# ZYNQ_PWR.net
KiCad netlist of a schematic drawn in Altium Designer
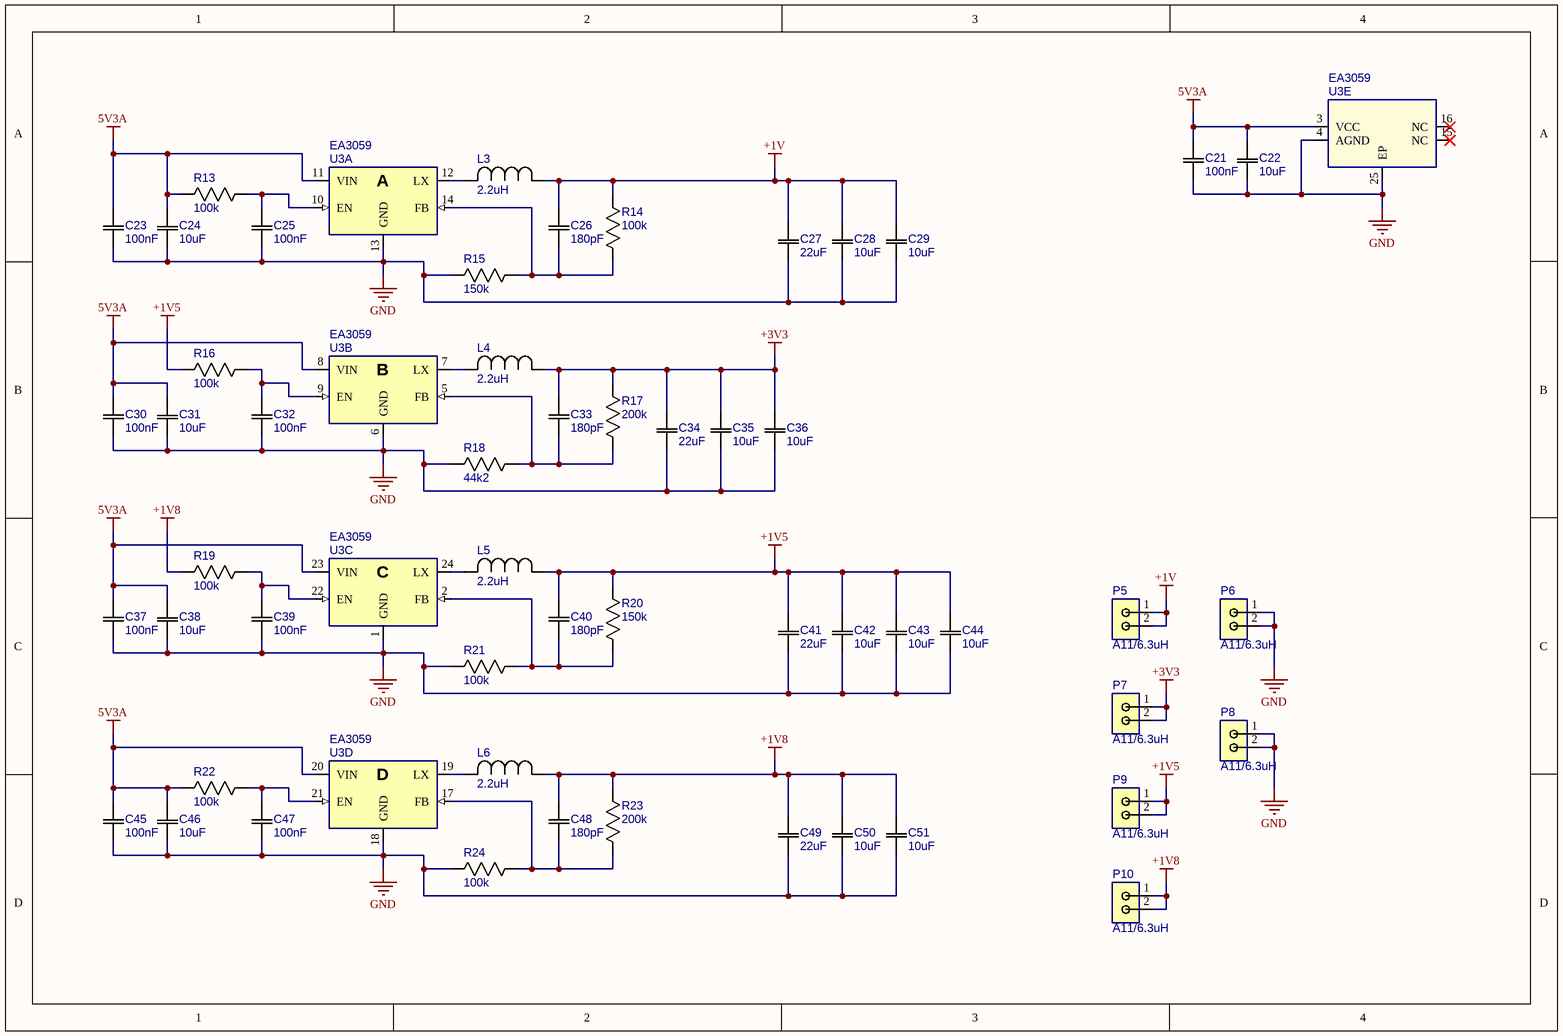
[diagram p0: ZYNQ_PWR.SchDoc]

(export (version "E")
  (design (tool "Eeschema 10.0.6"))
  (components
    (comp (ref "C21")
      (value "100nF")
      (footprint "0402")
      (description "GCM155R71H104ME02J\r\nMultilayer Ceramic Capacitors MLCC - SMD/SMT")
      (fields (field (name "MFR.") "Murata Electronics"))
      (libsource (lib "C0402") (part "GCM155R71H104ME02J"))
    )
    (comp (ref "C22")
      (value "10uF")
      (footprint "C0603")
      (description "OUDEIBUN\r\n50V 10% 106K X5R")
      (fields (field (name "MFR.") "OUDEIBUN"))
      (libsource (lib "C0603") (part "taobao_10uF"))
    )
    (comp (ref "C23")
      (value "100nF")
      (footprint "0402")
      (description "GCM155R71H104ME02J\r\nMultilayer Ceramic Capacitors MLCC - SMD/SMT")
      (fields (field (name "MFR.") "Murata Electronics"))
      (libsource (lib "C0402") (part "GCM155R71H104ME02J"))
    )
    (comp (ref "C24")
      (value "10uF")
      (footprint "C0603")
      (description "OUDEIBUN\r\n50V 10% 106K X5R")
      (fields (field (name "MFR.") "OUDEIBUN"))
      (libsource (lib "C0603") (part "taobao_10uF"))
    )
    (comp (ref "C25")
      (value "100nF")
      (footprint "0402")
      (description "GCM155R71H104ME02J\r\nMultilayer Ceramic Capacitors MLCC - SMD/SMT")
      (fields (field (name "MFR.") "Murata Electronics"))
      (libsource (lib "C0402") (part "GCM155R71H104ME02J"))
    )
    (comp (ref "C26")
      (value "180pF")
      (footprint "0402")
      (description "CL05C181JB5NNNC\r\n180pF(181) +/-5% 50V C0G")
      (fields (field (name "MFR.") "CL05C181JB5NNNC"))
      (libsource (lib "C0402") (part "CL05C181JB5NNNC"))
    )
    (comp (ref "C27")
      (value "22uF")
      (footprint "C0603")
      (description "OUDEIBUN\r\n25V 10% 226K X5R")
      (fields (field (name "MFR.") "OUDEIBUN"))
      (libsource (lib "C0603") (part "taobao_22uF"))
    )
    (comp (ref "C28")
      (value "10uF")
      (footprint "C0603")
      (description "OUDEIBUN\r\n50V 10% 106K X5R")
      (fields (field (name "MFR.") "OUDEIBUN"))
      (libsource (lib "C0603") (part "taobao_10uF"))
    )
    (comp (ref "C29")
      (value "10uF")
      (footprint "C0603")
      (description "OUDEIBUN\r\n50V 10% 106K X5R")
      (fields (field (name "MFR.") "OUDEIBUN"))
      (libsource (lib "C0603") (part "taobao_10uF"))
    )
    (comp (ref "C30")
      (value "100nF")
      (footprint "0402")
      (description "GCM155R71H104ME02J\r\nMultilayer Ceramic Capacitors MLCC - SMD/SMT")
      (fields (field (name "MFR.") "Murata Electronics"))
      (libsource (lib "C0402") (part "GCM155R71H104ME02J"))
    )
    (comp (ref "C31")
      (value "10uF")
      (footprint "C0603")
      (description "OUDEIBUN\r\n50V 10% 106K X5R")
      (fields (field (name "MFR.") "OUDEIBUN"))
      (libsource (lib "C0603") (part "taobao_10uF"))
    )
    (comp (ref "C32")
      (value "100nF")
      (footprint "0402")
      (description "GCM155R71H104ME02J\r\nMultilayer Ceramic Capacitors MLCC - SMD/SMT")
      (fields (field (name "MFR.") "Murata Electronics"))
      (libsource (lib "C0402") (part "GCM155R71H104ME02J"))
    )
    (comp (ref "C33")
      (value "180pF")
      (footprint "0402")
      (description "CL05C181JB5NNNC\r\n180pF(181) +/-5% 50V C0G")
      (fields (field (name "MFR.") "CL05C181JB5NNNC"))
      (libsource (lib "C0402") (part "CL05C181JB5NNNC"))
    )
    (comp (ref "C34")
      (value "22uF")
      (footprint "C0603")
      (description "OUDEIBUN\r\n25V 10% 226K X5R")
      (fields (field (name "MFR.") "OUDEIBUN"))
      (libsource (lib "C0603") (part "taobao_22uF"))
    )
    (comp (ref "C35")
      (value "10uF")
      (footprint "C0603")
      (description "OUDEIBUN\r\n50V 10% 106K X5R")
      (fields (field (name "MFR.") "OUDEIBUN"))
      (libsource (lib "C0603") (part "taobao_10uF"))
    )
    (comp (ref "C36")
      (value "10uF")
      (footprint "C0603")
      (description "OUDEIBUN\r\n50V 10% 106K X5R")
      (fields (field (name "MFR.") "OUDEIBUN"))
      (libsource (lib "C0603") (part "taobao_10uF"))
    )
    (comp (ref "C37")
      (value "100nF")
      (footprint "0402")
      (description "GCM155R71H104ME02J\r\nMultilayer Ceramic Capacitors MLCC - SMD/SMT")
      (fields (field (name "MFR.") "Murata Electronics"))
      (libsource (lib "C0402") (part "GCM155R71H104ME02J"))
    )
    (comp (ref "C38")
      (value "10uF")
      (footprint "C0603")
      (description "OUDEIBUN\r\n50V 10% 106K X5R")
      (fields (field (name "MFR.") "OUDEIBUN"))
      (libsource (lib "C0603") (part "taobao_10uF"))
    )
    (comp (ref "C39")
      (value "100nF")
      (footprint "0402")
      (description "GCM155R71H104ME02J\r\nMultilayer Ceramic Capacitors MLCC - SMD/SMT")
      (fields (field (name "MFR.") "Murata Electronics"))
      (libsource (lib "C0402") (part "GCM155R71H104ME02J"))
    )
    (comp (ref "C40")
      (value "180pF")
      (footprint "0402")
      (description "CL05C181JB5NNNC\r\n180pF(181) +/-5% 50V C0G")
      (fields (field (name "MFR.") "CL05C181JB5NNNC"))
      (libsource (lib "C0402") (part "CL05C181JB5NNNC"))
    )
    (comp (ref "C41")
      (value "22uF")
      (footprint "C0603")
      (description "OUDEIBUN\r\n25V 10% 226K X5R")
      (fields (field (name "MFR.") "OUDEIBUN"))
      (libsource (lib "C0603") (part "taobao_22uF"))
    )
    (comp (ref "C42")
      (value "10uF")
      (footprint "C0603")
      (description "OUDEIBUN\r\n50V 10% 106K X5R")
      (fields (field (name "MFR.") "OUDEIBUN"))
      (libsource (lib "C0603") (part "taobao_10uF"))
    )
    (comp (ref "C43")
      (value "10uF")
      (footprint "C0603")
      (description "OUDEIBUN\r\n50V 10% 106K X5R")
      (fields (field (name "MFR.") "OUDEIBUN"))
      (libsource (lib "C0603") (part "taobao_10uF"))
    )
    (comp (ref "C44")
      (value "10uF")
      (footprint "C0603")
      (description "OUDEIBUN\r\n50V 10% 106K X5R")
      (fields (field (name "MFR.") "OUDEIBUN"))
      (libsource (lib "C0603") (part "taobao_10uF"))
    )
    (comp (ref "C45")
      (value "100nF")
      (footprint "0402")
      (description "GCM155R71H104ME02J\r\nMultilayer Ceramic Capacitors MLCC - SMD/SMT")
      (fields (field (name "MFR.") "Murata Electronics"))
      (libsource (lib "C0402") (part "GCM155R71H104ME02J"))
    )
    (comp (ref "C46")
      (value "10uF")
      (footprint "C0603")
      (description "OUDEIBUN\r\n50V 10% 106K X5R")
      (fields (field (name "MFR.") "OUDEIBUN"))
      (libsource (lib "C0603") (part "taobao_10uF"))
    )
    (comp (ref "C47")
      (value "100nF")
      (footprint "0402")
      (description "GCM155R71H104ME02J\r\nMultilayer Ceramic Capacitors MLCC - SMD/SMT")
      (fields (field (name "MFR.") "Murata Electronics"))
      (libsource (lib "C0402") (part "GCM155R71H104ME02J"))
    )
    (comp (ref "C48")
      (value "180pF")
      (footprint "0402")
      (description "CL05C181JB5NNNC\r\n180pF(181) +/-5% 50V C0G")
      (fields (field (name "MFR.") "CL05C181JB5NNNC"))
      (libsource (lib "C0402") (part "CL05C181JB5NNNC"))
    )
    (comp (ref "C49")
      (value "22uF")
      (footprint "C0603")
      (description "OUDEIBUN\r\n25V 10% 226K X5R")
      (fields (field (name "MFR.") "OUDEIBUN"))
      (libsource (lib "C0603") (part "taobao_22uF"))
    )
    (comp (ref "C50")
      (value "10uF")
      (footprint "C0603")
      (description "OUDEIBUN\r\n50V 10% 106K X5R")
      (fields (field (name "MFR.") "OUDEIBUN"))
      (libsource (lib "C0603") (part "taobao_10uF"))
    )
    (comp (ref "C51")
      (value "10uF")
      (footprint "C0603")
      (description "OUDEIBUN\r\n50V 10% 106K X5R")
      (fields (field (name "MFR.") "OUDEIBUN"))
      (libsource (lib "C0603") (part "taobao_10uF"))
    )
    (comp (ref "L3")
      (value "2.2uH")
      (footprint "04x0SMD")
      (description "4.6mmx4.1mm (LxH) DCDC Inductor SMD")
      (fields (field (name "MFR.") "Your Cee"))
      (libsource (lib "L04x0") (part "L0420"))
    )
    (comp (ref "L4")
      (value "2.2uH")
      (footprint "04x0SMD")
      (description "4.6mmx4.1mm (LxH) DCDC Inductor SMD")
      (fields (field (name "MFR.") "Your Cee"))
      (libsource (lib "L04x0") (part "L0420"))
    )
    (comp (ref "L5")
      (value "2.2uH")
      (footprint "04x0SMD")
      (description "4.6mmx4.1mm (LxH) DCDC Inductor SMD")
      (fields (field (name "MFR.") "Your Cee"))
      (libsource (lib "L04x0") (part "L0420"))
    )
    (comp (ref "L6")
      (value "2.2uH")
      (footprint "04x0SMD")
      (description "4.6mmx4.1mm (LxH) DCDC Inductor SMD")
      (fields (field (name "MFR.") "Your Cee"))
      (libsource (lib "L04x0") (part "L0420"))
    )
    (comp (ref "P5")
      (value "A11/6.3uH")
      (footprint "2x3mmPad")
      (description "A11_QI_6u3H_DUAL")
      (fields (field (name "MFR.") "Huihai Longteng"))
      (libsource (lib "contact_pin") (part "A11_QI_6u3H_DUAL"))
    )
    (comp (ref "P6")
      (value "A11/6.3uH")
      (footprint "2x3mmPad")
      (description "A11_QI_6u3H_DUAL")
      (fields (field (name "MFR.") "Huihai Longteng"))
      (libsource (lib "contact_pin") (part "A11_QI_6u3H_DUAL"))
    )
    (comp (ref "P7")
      (value "A11/6.3uH")
      (footprint "2x3mmPad")
      (description "A11_QI_6u3H_DUAL")
      (fields (field (name "MFR.") "Huihai Longteng"))
      (libsource (lib "contact_pin") (part "A11_QI_6u3H_DUAL"))
    )
    (comp (ref "P8")
      (value "A11/6.3uH")
      (footprint "2x3mmPad")
      (description "A11_QI_6u3H_DUAL")
      (fields (field (name "MFR.") "Huihai Longteng"))
      (libsource (lib "contact_pin") (part "A11_QI_6u3H_DUAL"))
    )
    (comp (ref "P9")
      (value "A11/6.3uH")
      (footprint "2x3mmPad")
      (description "A11_QI_6u3H_DUAL")
      (fields (field (name "MFR.") "Huihai Longteng"))
      (libsource (lib "contact_pin") (part "A11_QI_6u3H_DUAL"))
    )
    (comp (ref "P10")
      (value "A11/6.3uH")
      (footprint "2x3mmPad")
      (description "A11_QI_6u3H_DUAL")
      (fields (field (name "MFR.") "Huihai Longteng"))
      (libsource (lib "contact_pin") (part "A11_QI_6u3H_DUAL"))
    )
    (comp (ref "R13")
      (value "100k")
      (footprint "0402")
      (description "OUDEIBUN\r\n1% 100k")
      (fields (field (name "MFR.") "UNIOHM"))
      (libsource (lib "R0402") (part "taobao_100k"))
    )
    (comp (ref "R14")
      (value "100k")
      (footprint "0402")
      (description "OUDEIBUN\r\n1% 100k")
      (fields (field (name "MFR.") "UNIOHM"))
      (libsource (lib "R0402") (part "taobao_100k"))
    )
    (comp (ref "R15")
      (value "150k")
      (footprint "0402")
      (description "OUDEIBUN\r\n1% 150k")
      (fields (field (name "MFR.") "UNIOHM"))
      (libsource (lib "R0402") (part "taobao_150k"))
    )
    (comp (ref "R16")
      (value "100k")
      (footprint "0402")
      (description "OUDEIBUN\r\n1% 100k")
      (fields (field (name "MFR.") "UNIOHM"))
      (libsource (lib "R0402") (part "taobao_100k"))
    )
    (comp (ref "R17")
      (value "200k")
      (footprint "0402")
      (description "OUDEIBUN\r\n1% 200k")
      (fields (field (name "MFR.") "OUDEIBUN"))
      (libsource (lib "R0402") (part "taobao_200k"))
    )
    (comp (ref "R18")
      (value "44k2")
      (footprint "0402")
      (description "UNIOHM\r\n44k2 1% 1/16W")
      (fields (field (name "MFR.") "UNIOHM"))
      (libsource (lib "R0402") (part "taobao_44k2"))
    )
    (comp (ref "R19")
      (value "100k")
      (footprint "0402")
      (description "OUDEIBUN\r\n1% 100k")
      (fields (field (name "MFR.") "UNIOHM"))
      (libsource (lib "R0402") (part "taobao_100k"))
    )
    (comp (ref "R20")
      (value "150k")
      (footprint "0402")
      (description "OUDEIBUN\r\n1% 150k")
      (fields (field (name "MFR.") "UNIOHM"))
      (libsource (lib "R0402") (part "taobao_150k"))
    )
    (comp (ref "R21")
      (value "100k")
      (footprint "0402")
      (description "OUDEIBUN\r\n1% 100k")
      (fields (field (name "MFR.") "UNIOHM"))
      (libsource (lib "R0402") (part "taobao_100k"))
    )
    (comp (ref "R22")
      (value "100k")
      (footprint "0402")
      (description "OUDEIBUN\r\n1% 100k")
      (fields (field (name "MFR.") "UNIOHM"))
      (libsource (lib "R0402") (part "taobao_100k"))
    )
    (comp (ref "R23")
      (value "200k")
      (footprint "0402")
      (description "OUDEIBUN\r\n1% 200k")
      (fields (field (name "MFR.") "OUDEIBUN"))
      (libsource (lib "R0402") (part "taobao_200k"))
    )
    (comp (ref "R24")
      (value "100k")
      (footprint "0402")
      (description "OUDEIBUN\r\n1% 100k")
      (fields (field (name "MFR.") "UNIOHM"))
      (libsource (lib "R0402") (part "taobao_100k"))
    )
    (comp (ref "U3")
      (value "EA3059")
      (footprint "QFN-24")
      (fields (field (name "MFR.") "EverAnalog"))
      (libsource (lib "everanalog") (part "EA3059"))
    )
  )
  (nets
    (net (code "1") (name "+1V") (class "Default")
      (node (ref "C26") (pin "1") (pinfunction "1_1") (pintype "passive"))
      (node (ref "C27") (pin "2") (pinfunction "2_2") (pintype "passive"))
      (node (ref "C28") (pin "2") (pinfunction "2_2") (pintype "passive"))
      (node (ref "C29") (pin "2") (pinfunction "2_2") (pintype "passive"))
      (node (ref "L3") (pin "1") (pinfunction "1_1") (pintype "passive"))
      (node (ref "P5") (pin "1") (pinfunction "P0_1") (pintype "passive"))
      (node (ref "P5") (pin "2") (pinfunction "P1_2") (pintype "passive"))
      (node (ref "R14") (pin "2") (pinfunction "2_2") (pintype "passive"))
    )
    (net (code "2") (name "+1V5") (class "Default")
      (node (ref "C40") (pin "1") (pinfunction "1_1") (pintype "passive"))
      (node (ref "C41") (pin "2") (pinfunction "2_2") (pintype "passive"))
      (node (ref "C42") (pin "2") (pinfunction "2_2") (pintype "passive"))
      (node (ref "C43") (pin "2") (pinfunction "2_2") (pintype "passive"))
      (node (ref "C44") (pin "2") (pinfunction "2_2") (pintype "passive"))
      (node (ref "L5") (pin "1") (pinfunction "1_1") (pintype "passive"))
      (node (ref "P9") (pin "1") (pinfunction "P0_1") (pintype "passive"))
      (node (ref "P9") (pin "2") (pinfunction "P1_2") (pintype "passive"))
      (node (ref "R16") (pin "1") (pinfunction "1_1") (pintype "passive"))
      (node (ref "R20") (pin "2") (pinfunction "2_2") (pintype "passive"))
    )
    (net (code "3") (name "+1V8") (class "Default")
      (node (ref "C48") (pin "1") (pinfunction "1_1") (pintype "passive"))
      (node (ref "C49") (pin "2") (pinfunction "2_2") (pintype "passive"))
      (node (ref "C50") (pin "2") (pinfunction "2_2") (pintype "passive"))
      (node (ref "C51") (pin "2") (pinfunction "2_2") (pintype "passive"))
      (node (ref "L6") (pin "1") (pinfunction "1_1") (pintype "passive"))
      (node (ref "P10") (pin "1") (pinfunction "P0_1") (pintype "passive"))
      (node (ref "P10") (pin "2") (pinfunction "P1_2") (pintype "passive"))
      (node (ref "R19") (pin "1") (pinfunction "1_1") (pintype "passive"))
      (node (ref "R23") (pin "2") (pinfunction "2_2") (pintype "passive"))
    )
    (net (code "4") (name "+3V3") (class "Default")
      (node (ref "C33") (pin "1") (pinfunction "1_1") (pintype "passive"))
      (node (ref "C34") (pin "2") (pinfunction "2_2") (pintype "passive"))
      (node (ref "C35") (pin "2") (pinfunction "2_2") (pintype "passive"))
      (node (ref "C36") (pin "2") (pinfunction "2_2") (pintype "passive"))
      (node (ref "L4") (pin "1") (pinfunction "1_1") (pintype "passive"))
      (node (ref "P7") (pin "1") (pinfunction "P0_1") (pintype "passive"))
      (node (ref "P7") (pin "2") (pinfunction "P1_2") (pintype "passive"))
      (node (ref "R17") (pin "2") (pinfunction "2_2") (pintype "passive"))
    )
    (net (code "5") (name "5V3A") (class "Default")
      (node (ref "C21") (pin "1") (pinfunction "1_1") (pintype "passive"))
      (node (ref "C22") (pin "2") (pinfunction "2_2") (pintype "passive"))
      (node (ref "C23") (pin "1") (pinfunction "1_1") (pintype "passive"))
      (node (ref "C24") (pin "2") (pinfunction "2_2") (pintype "passive"))
      (node (ref "C30") (pin "1") (pinfunction "1_1") (pintype "passive"))
      (node (ref "C31") (pin "2") (pinfunction "2_2") (pintype "passive"))
      (node (ref "C37") (pin "1") (pinfunction "1_1") (pintype "passive"))
      (node (ref "C38") (pin "2") (pinfunction "2_2") (pintype "passive"))
      (node (ref "C45") (pin "1") (pinfunction "1_1") (pintype "passive"))
      (node (ref "C46") (pin "2") (pinfunction "2_2") (pintype "passive"))
      (node (ref "R13") (pin "1") (pinfunction "1_1") (pintype "passive"))
      (node (ref "R22") (pin "1") (pinfunction "1_1") (pintype "passive"))
      (node (ref "U3") (pin "11") (pinfunction "VIN_11") (pintype "power_in"))
      (node (ref "U3") (pin "20") (pinfunction "VIN_20") (pintype "power_in"))
      (node (ref "U3") (pin "23") (pinfunction "VIN_23") (pintype "power_in"))
      (node (ref "U3") (pin "3") (pinfunction "VCC_3") (pintype "power_in"))
      (node (ref "U3") (pin "8") (pinfunction "VIN_8") (pintype "power_in"))
    )
    (net (code "6") (name "GND") (class "Default")
      (node (ref "C21") (pin "2") (pinfunction "2_2") (pintype "passive"))
      (node (ref "C22") (pin "1") (pinfunction "1_1") (pintype "passive"))
      (node (ref "C23") (pin "2") (pinfunction "2_2") (pintype "passive"))
      (node (ref "C24") (pin "1") (pinfunction "1_1") (pintype "passive"))
      (node (ref "C25") (pin "2") (pinfunction "2_2") (pintype "passive"))
      (node (ref "C27") (pin "1") (pinfunction "1_1") (pintype "passive"))
      (node (ref "C28") (pin "1") (pinfunction "1_1") (pintype "passive"))
      (node (ref "C29") (pin "1") (pinfunction "1_1") (pintype "passive"))
      (node (ref "C30") (pin "2") (pinfunction "2_2") (pintype "passive"))
      (node (ref "C31") (pin "1") (pinfunction "1_1") (pintype "passive"))
      (node (ref "C32") (pin "2") (pinfunction "2_2") (pintype "passive"))
      (node (ref "C34") (pin "1") (pinfunction "1_1") (pintype "passive"))
      (node (ref "C35") (pin "1") (pinfunction "1_1") (pintype "passive"))
      (node (ref "C36") (pin "1") (pinfunction "1_1") (pintype "passive"))
      (node (ref "C37") (pin "2") (pinfunction "2_2") (pintype "passive"))
      (node (ref "C38") (pin "1") (pinfunction "1_1") (pintype "passive"))
      (node (ref "C39") (pin "2") (pinfunction "2_2") (pintype "passive"))
      (node (ref "C41") (pin "1") (pinfunction "1_1") (pintype "passive"))
      (node (ref "C42") (pin "1") (pinfunction "1_1") (pintype "passive"))
      (node (ref "C43") (pin "1") (pinfunction "1_1") (pintype "passive"))
      (node (ref "C44") (pin "1") (pinfunction "1_1") (pintype "passive"))
      (node (ref "C45") (pin "2") (pinfunction "2_2") (pintype "passive"))
      (node (ref "C46") (pin "1") (pinfunction "1_1") (pintype "passive"))
      (node (ref "C47") (pin "2") (pinfunction "2_2") (pintype "passive"))
      (node (ref "C49") (pin "1") (pinfunction "1_1") (pintype "passive"))
      (node (ref "C50") (pin "1") (pinfunction "1_1") (pintype "passive"))
      (node (ref "C51") (pin "1") (pinfunction "1_1") (pintype "passive"))
      (node (ref "P6") (pin "1") (pinfunction "P0_1") (pintype "passive"))
      (node (ref "P6") (pin "2") (pinfunction "P1_2") (pintype "passive"))
      (node (ref "P8") (pin "1") (pinfunction "P0_1") (pintype "passive"))
      (node (ref "P8") (pin "2") (pinfunction "P1_2") (pintype "passive"))
      (node (ref "R15") (pin "2") (pinfunction "2_2") (pintype "passive"))
      (node (ref "R18") (pin "1") (pinfunction "1_1") (pintype "passive"))
      (node (ref "R21") (pin "1") (pinfunction "1_1") (pintype "passive"))
      (node (ref "R24") (pin "2") (pinfunction "2_2") (pintype "passive"))
      (node (ref "U3") (pin "1") (pinfunction "GND_1") (pintype "power_in"))
      (node (ref "U3") (pin "13") (pinfunction "GND_13") (pintype "power_in"))
      (node (ref "U3") (pin "18") (pinfunction "GND_18") (pintype "power_in"))
      (node (ref "U3") (pin "25") (pinfunction "EP_25") (pintype "power_in"))
      (node (ref "U3") (pin "4") (pinfunction "AGND_4") (pintype "power_in"))
      (node (ref "U3") (pin "6") (pinfunction "GND_6") (pintype "power_in"))
    )
    (net (code "7") (name "Net-(U3A-EN)") (class "Default")
      (node (ref "C25") (pin "1") (pinfunction "1_1") (pintype "passive"))
      (node (ref "R13") (pin "2") (pinfunction "2_2") (pintype "passive"))
      (node (ref "U3") (pin "10") (pinfunction "EN_10") (pintype "input"))
    )
    (net (code "8") (name "Net-(U3A-FB)") (class "Default")
      (node (ref "C26") (pin "2") (pinfunction "2_2") (pintype "passive"))
      (node (ref "R14") (pin "1") (pinfunction "1_1") (pintype "passive"))
      (node (ref "R15") (pin "1") (pinfunction "1_1") (pintype "passive"))
      (node (ref "U3") (pin "14") (pinfunction "FB_14") (pintype "input"))
    )
    (net (code "9") (name "Net-(U3A-LX)") (class "Default")
      (node (ref "L3") (pin "2") (pinfunction "2_2") (pintype "passive"))
      (node (ref "U3") (pin "12") (pinfunction "LX_12") (pintype "power_in"))
    )
    (net (code "10") (name "Net-(U3B-EN)") (class "Default")
      (node (ref "C32") (pin "1") (pinfunction "1_1") (pintype "passive"))
      (node (ref "R16") (pin "2") (pinfunction "2_2") (pintype "passive"))
      (node (ref "U3") (pin "9") (pinfunction "EN_9") (pintype "input"))
    )
    (net (code "11") (name "Net-(U3B-FB)") (class "Default")
      (node (ref "C33") (pin "2") (pinfunction "2_2") (pintype "passive"))
      (node (ref "R17") (pin "1") (pinfunction "1_1") (pintype "passive"))
      (node (ref "R18") (pin "2") (pinfunction "2_2") (pintype "passive"))
      (node (ref "U3") (pin "5") (pinfunction "FB_5") (pintype "input"))
    )
    (net (code "12") (name "Net-(U3B-LX)") (class "Default")
      (node (ref "L4") (pin "2") (pinfunction "2_2") (pintype "passive"))
      (node (ref "U3") (pin "7") (pinfunction "LX_7") (pintype "power_in"))
    )
    (net (code "13") (name "Net-(U3C-EN)") (class "Default")
      (node (ref "C39") (pin "1") (pinfunction "1_1") (pintype "passive"))
      (node (ref "R19") (pin "2") (pinfunction "2_2") (pintype "passive"))
      (node (ref "U3") (pin "22") (pinfunction "EN_22") (pintype "input"))
    )
    (net (code "14") (name "Net-(U3C-FB)") (class "Default")
      (node (ref "C40") (pin "2") (pinfunction "2_2") (pintype "passive"))
      (node (ref "R20") (pin "1") (pinfunction "1_1") (pintype "passive"))
      (node (ref "R21") (pin "2") (pinfunction "2_2") (pintype "passive"))
      (node (ref "U3") (pin "2") (pinfunction "FB_2") (pintype "input"))
    )
    (net (code "15") (name "Net-(U3C-LX)") (class "Default")
      (node (ref "L5") (pin "2") (pinfunction "2_2") (pintype "passive"))
      (node (ref "U3") (pin "24") (pinfunction "LX_24") (pintype "power_in"))
    )
    (net (code "16") (name "Net-(U3D-EN)") (class "Default")
      (node (ref "C47") (pin "1") (pinfunction "1_1") (pintype "passive"))
      (node (ref "R22") (pin "2") (pinfunction "2_2") (pintype "passive"))
      (node (ref "U3") (pin "21") (pinfunction "EN_21") (pintype "input"))
    )
    (net (code "17") (name "Net-(U3D-FB)") (class "Default")
      (node (ref "C48") (pin "2") (pinfunction "2_2") (pintype "passive"))
      (node (ref "R23") (pin "1") (pinfunction "1_1") (pintype "passive"))
      (node (ref "R24") (pin "1") (pinfunction "1_1") (pintype "passive"))
      (node (ref "U3") (pin "17") (pinfunction "FB_17") (pintype "input"))
    )
    (net (code "18") (name "Net-(U3D-LX)") (class "Default")
      (node (ref "L6") (pin "2") (pinfunction "2_2") (pintype "passive"))
      (node (ref "U3") (pin "19") (pinfunction "LX_19") (pintype "power_in"))
    )
    (net (code "19") (name "unconnected-(U3E-NC-Pad15)") (class "Default")
      (node (ref "U3") (pin "15") (pinfunction "NC_15") (pintype "passive+no_connect"))
    )
    (net (code "20") (name "unconnected-(U3E-NC-Pad16)") (class "Default")
      (node (ref "U3") (pin "16") (pinfunction "NC_16") (pintype "passive+no_connect"))
    )
  )
)
